# Air_quality_sensor.net
KiCad netlist of a schematic drawn in Altium Designer
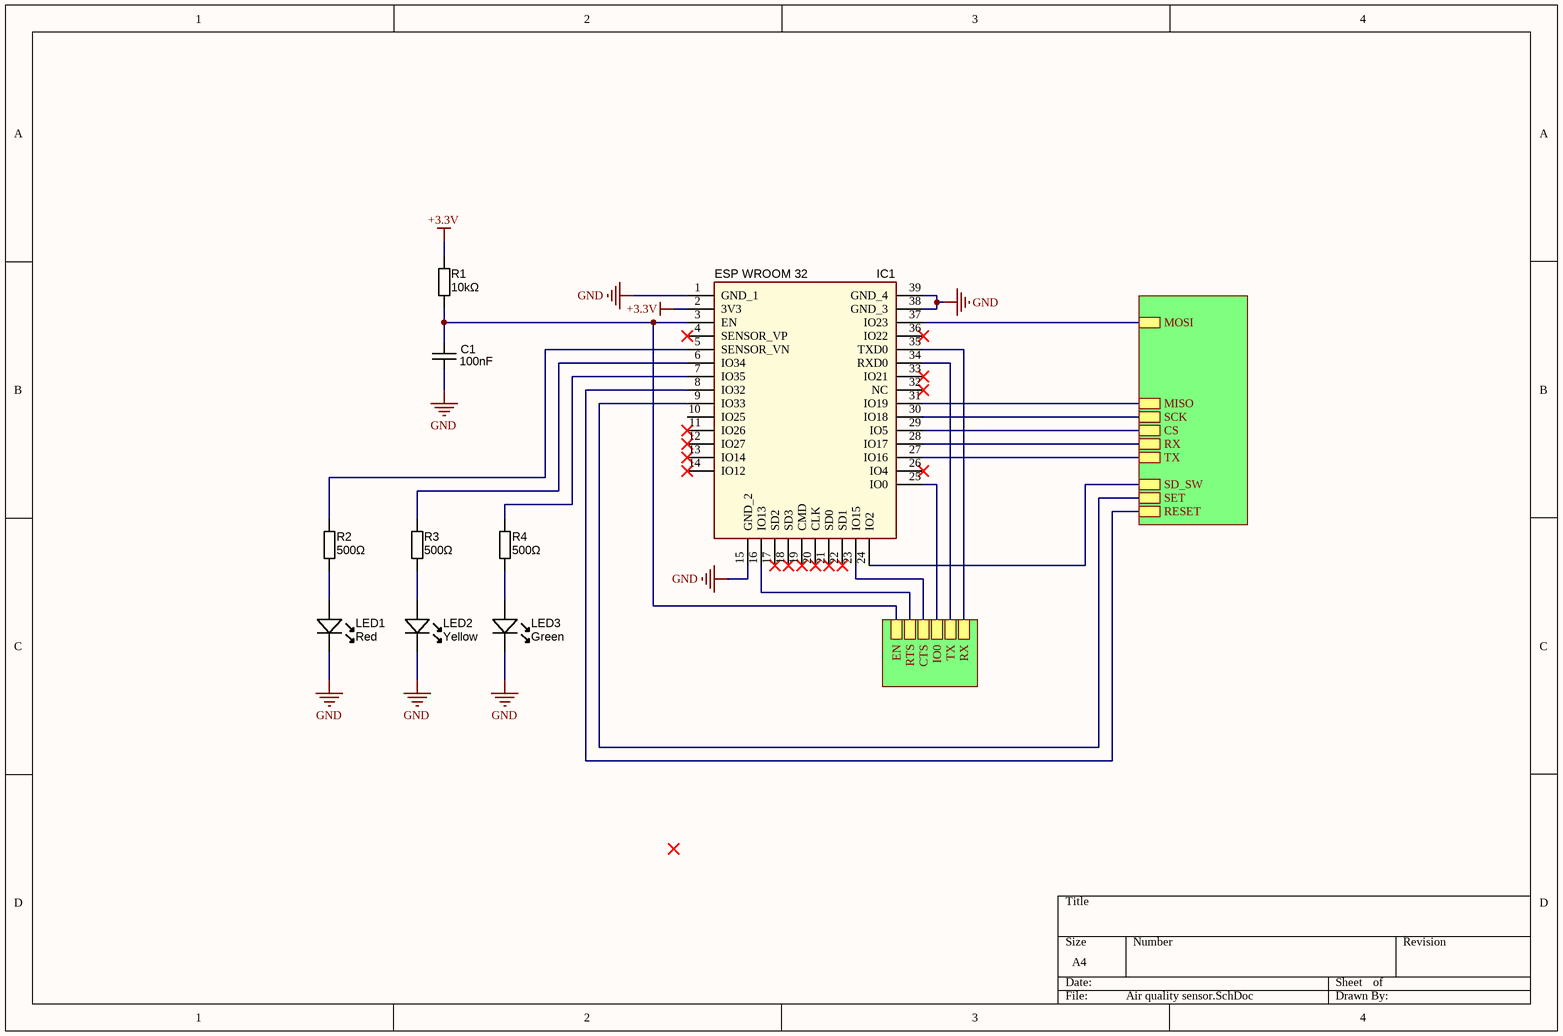
[diagram p0: Air quality sensor.SchDoc]

(export (version "E")
  (design (tool "Eeschema 10.0.6"))
  (components
    (comp (ref "C1")
      (value "100nF")
      (footprint "CAPC1608N")
      (description "Capacitor SMD Cer 1uF 10% 16V X7R 0603")
      (fields (field (name "TOLERANCE") "±10%") (field (name "Comment") "approved sub OK"))
      (libsource (lib "Nejc Klanjšček") (part "CAPC_1u_0603"))
    )
    (comp (ref "IC1")
      (value "ESP WROOM 32")
      (footprint "ESP32WROOM32D")
      (description "Integrated Circuit")
      (fields
        (field (name "MANUFACTURER_PART_NUMBER") "ESP-WROOM-32 (16MB)")
        (field (name "MOUSER PART NUMBER") "356-ESPWROOM3216MB")
      )
      (libsource (lib "Nejc Klanjšček") (part "ESP-WROOM-32__16MB_"))
    )
    (comp (ref "LED1")
      (value "Red")
      (footprint "LED-0603-WHITE")
      (description "LED 0603 SMD White 8700K 108.5mcd 5mA")
      (libsource (lib "Nejc Klanjšček") (part "LED_SMD_White_0603_109mcd"))
    )
    (comp (ref "LED2")
      (value "Yellow")
      (footprint "LED-0603-WHITE")
      (description "LED 0603 SMD White 8700K 108.5mcd 5mA")
      (libsource (lib "Nejc Klanjšček") (part "LED_SMD_White_0603_109mcd"))
    )
    (comp (ref "LED3")
      (value "Green")
      (footprint "LED-0603-WHITE")
      (description "LED 0603 SMD White 8700K 108.5mcd 5mA")
      (libsource (lib "Nejc Klanjšček") (part "LED_SMD_White_0603_109mcd"))
    )
    (comp (ref "R1")
      (value "10kΩ")
      (footprint "RESC1608N")
      (description "Resistor SMD chip 1.5k Ohm 0.1W 5% 0603")
      (fields (field (name "TOLERANCE") "±5%") (field (name "Comment") "Thick Film"))
      (libsource (lib "Nejc Klanjšček") (part "RES_1K5_0603_5%"))
    )
    (comp (ref "R2")
      (value "500Ω")
      (footprint "RESC1608N")
      (description "Resistor SMD chip 1.5k Ohm 0.1W 5% 0603")
      (fields (field (name "TOLERANCE") "±5%") (field (name "Comment") "Thick Film"))
      (libsource (lib "Nejc Klanjšček") (part "RES_1K5_0603_5%"))
    )
    (comp (ref "R3")
      (value "500Ω")
      (footprint "RESC1608N")
      (description "Resistor SMD chip 1.5k Ohm 0.1W 5% 0603")
      (fields (field (name "TOLERANCE") "±5%") (field (name "Comment") "Thick Film"))
      (libsource (lib "Nejc Klanjšček") (part "RES_1K5_0603_5%"))
    )
    (comp (ref "R4")
      (value "500Ω")
      (footprint "RESC1608N")
      (description "Resistor SMD chip 1.5k Ohm 0.1W 5% 0603")
      (fields (field (name "TOLERANCE") "±5%") (field (name "Comment") "Thick Film"))
      (libsource (lib "Nejc Klanjšček") (part "RES_1K5_0603_5%"))
    )
  )
  (nets
    (net (code "1") (name "+3.3V") (class "Default")
      (node (ref "IC1") (pin "2") (pinfunction "3V3_2") (pintype "passive"))
      (node (ref "R1") (pin "1") (pinfunction "1_1") (pintype "passive"))
    )
    (net (code "2") (name "/CS") (class "Default")
      (node (ref "IC1") (pin "29") (pinfunction "IO5_29") (pintype "passive"))
    )
    (net (code "3") (name "/CTS") (class "Default")
      (node (ref "IC1") (pin "23") (pinfunction "IO15_23") (pintype "passive"))
    )
    (net (code "4") (name "/EN") (class "Default")
      (node (ref "C1") (pin "2") (pintype "passive"))
      (node (ref "IC1") (pin "3") (pinfunction "EN_3") (pintype "passive"))
      (node (ref "R1") (pin "2") (pinfunction "2_2") (pintype "passive"))
    )
    (net (code "5") (name "/IO0") (class "Default")
      (node (ref "IC1") (pin "25") (pinfunction "IO0_25") (pintype "passive"))
    )
    (net (code "6") (name "/MISO") (class "Default")
      (node (ref "IC1") (pin "31") (pinfunction "IO19_31") (pintype "passive"))
    )
    (net (code "7") (name "/MOSI") (class "Default")
      (node (ref "IC1") (pin "37") (pinfunction "IO23_37") (pintype "passive"))
    )
    (net (code "8") (name "/RESET") (class "Default")
      (node (ref "IC1") (pin "8") (pinfunction "IO32_8") (pintype "passive"))
    )
    (net (code "9") (name "/RTS") (class "Default")
      (node (ref "IC1") (pin "16") (pinfunction "IO13_16") (pintype "passive"))
    )
    (net (code "10") (name "/RX") (class "Default")
      (node (ref "IC1") (pin "28") (pinfunction "IO17_28") (pintype "passive"))
    )
    (net (code "11") (name "/RX_1") (class "Default")
      (node (ref "IC1") (pin "35") (pinfunction "TXD0_35") (pintype "passive"))
    )
    (net (code "12") (name "/SCK") (class "Default")
      (node (ref "IC1") (pin "30") (pinfunction "IO18_30") (pintype "passive"))
    )
    (net (code "13") (name "/SD_SW") (class "Default")
      (node (ref "IC1") (pin "24") (pinfunction "IO2_24") (pintype "passive"))
    )
    (net (code "14") (name "/SET") (class "Default")
      (node (ref "IC1") (pin "9") (pinfunction "IO33_9") (pintype "passive"))
    )
    (net (code "15") (name "/TX") (class "Default")
      (node (ref "IC1") (pin "27") (pinfunction "IO16_27") (pintype "passive"))
    )
    (net (code "16") (name "/TX_1") (class "Default")
      (node (ref "IC1") (pin "34") (pinfunction "RXD0_34") (pintype "passive"))
    )
    (net (code "17") (name "GND") (class "Default")
      (node (ref "C1") (pin "1") (pintype "passive"))
      (node (ref "IC1") (pin "1") (pinfunction "GND_1_1") (pintype "passive"))
      (node (ref "IC1") (pin "15") (pinfunction "GND_2_15") (pintype "passive"))
      (node (ref "IC1") (pin "38") (pinfunction "GND_3_38") (pintype "passive"))
      (node (ref "IC1") (pin "39") (pinfunction "GND_4_39") (pintype "passive"))
      (node (ref "LED1") (pin "K") (pinfunction "K_K") (pintype "passive"))
      (node (ref "LED2") (pin "K") (pinfunction "K_K") (pintype "passive"))
      (node (ref "LED3") (pin "K") (pinfunction "K_K") (pintype "passive"))
    )
    (net (code "18") (name "Net-(IC1-IO34)") (class "Default")
      (node (ref "IC1") (pin "6") (pinfunction "IO34_6") (pintype "passive"))
      (node (ref "R3") (pin "1") (pinfunction "1_1") (pintype "passive"))
    )
    (net (code "19") (name "Net-(IC1-IO35)") (class "Default")
      (node (ref "IC1") (pin "7") (pinfunction "IO35_7") (pintype "passive"))
      (node (ref "R4") (pin "1") (pinfunction "1_1") (pintype "passive"))
    )
    (net (code "20") (name "Net-(IC1-SENSOR_VN)") (class "Default")
      (node (ref "IC1") (pin "5") (pinfunction "SENSOR_VN_5") (pintype "passive"))
      (node (ref "R2") (pin "1") (pinfunction "1_1") (pintype "passive"))
    )
    (net (code "21") (name "Net-(LED1-PadA)") (class "Default")
      (node (ref "LED1") (pin "A") (pinfunction "A_A") (pintype "passive"))
      (node (ref "R2") (pin "2") (pinfunction "2_2") (pintype "passive"))
    )
    (net (code "22") (name "Net-(LED2-PadA)") (class "Default")
      (node (ref "LED2") (pin "A") (pinfunction "A_A") (pintype "passive"))
      (node (ref "R3") (pin "2") (pinfunction "2_2") (pintype "passive"))
    )
    (net (code "23") (name "Net-(LED3-PadA)") (class "Default")
      (node (ref "LED3") (pin "A") (pinfunction "A_A") (pintype "passive"))
      (node (ref "R4") (pin "2") (pinfunction "2_2") (pintype "passive"))
    )
    (net (code "24") (name "unconnected-(IC1-CLK-Pad20)") (class "Default")
      (node (ref "IC1") (pin "20") (pinfunction "CLK_20") (pintype "passive+no_connect"))
    )
    (net (code "25") (name "unconnected-(IC1-CMD-Pad19)") (class "Default")
      (node (ref "IC1") (pin "19") (pinfunction "CMD_19") (pintype "passive+no_connect"))
    )
    (net (code "26") (name "unconnected-(IC1-IO4-Pad26)") (class "Default")
      (node (ref "IC1") (pin "26") (pinfunction "IO4_26") (pintype "passive+no_connect"))
    )
    (net (code "27") (name "unconnected-(IC1-IO12-Pad14)") (class "Default")
      (node (ref "IC1") (pin "14") (pinfunction "IO12_14") (pintype "passive+no_connect"))
    )
    (net (code "28") (name "unconnected-(IC1-IO14-Pad13)") (class "Default")
      (node (ref "IC1") (pin "13") (pinfunction "IO14_13") (pintype "passive+no_connect"))
    )
    (net (code "29") (name "unconnected-(IC1-IO21-Pad33)") (class "Default")
      (node (ref "IC1") (pin "33") (pinfunction "IO21_33") (pintype "passive+no_connect"))
    )
    (net (code "30") (name "unconnected-(IC1-IO22-Pad36)") (class "Default")
      (node (ref "IC1") (pin "36") (pinfunction "IO22_36") (pintype "passive+no_connect"))
    )
    (net (code "31") (name "unconnected-(IC1-IO25-Pad10)") (class "Default")
      (node (ref "IC1") (pin "10") (pinfunction "IO25_10") (pintype "passive"))
    )
    (net (code "32") (name "unconnected-(IC1-IO26-Pad11)") (class "Default")
      (node (ref "IC1") (pin "11") (pinfunction "IO26_11") (pintype "passive+no_connect"))
    )
    (net (code "33") (name "unconnected-(IC1-IO27-Pad12)") (class "Default")
      (node (ref "IC1") (pin "12") (pinfunction "IO27_12") (pintype "passive+no_connect"))
    )
    (net (code "34") (name "unconnected-(IC1-NC-Pad32)") (class "Default")
      (node (ref "IC1") (pin "32") (pinfunction "NC_32") (pintype "passive+no_connect"))
    )
    (net (code "35") (name "unconnected-(IC1-SD0-Pad21)") (class "Default")
      (node (ref "IC1") (pin "21") (pinfunction "SD0_21") (pintype "passive+no_connect"))
    )
    (net (code "36") (name "unconnected-(IC1-SD1-Pad22)") (class "Default")
      (node (ref "IC1") (pin "22") (pinfunction "SD1_22") (pintype "passive+no_connect"))
    )
    (net (code "37") (name "unconnected-(IC1-SD2-Pad17)") (class "Default")
      (node (ref "IC1") (pin "17") (pinfunction "SD2_17") (pintype "passive+no_connect"))
    )
    (net (code "38") (name "unconnected-(IC1-SD3-Pad18)") (class "Default")
      (node (ref "IC1") (pin "18") (pinfunction "SD3_18") (pintype "passive+no_connect"))
    )
    (net (code "39") (name "unconnected-(IC1-SENSOR_VP-Pad4)") (class "Default")
      (node (ref "IC1") (pin "4") (pinfunction "SENSOR_VP_4") (pintype "passive+no_connect"))
    )
  )
)
